# she_atmega328.net
KiCad netlist of a schematic drawn in EAGLE
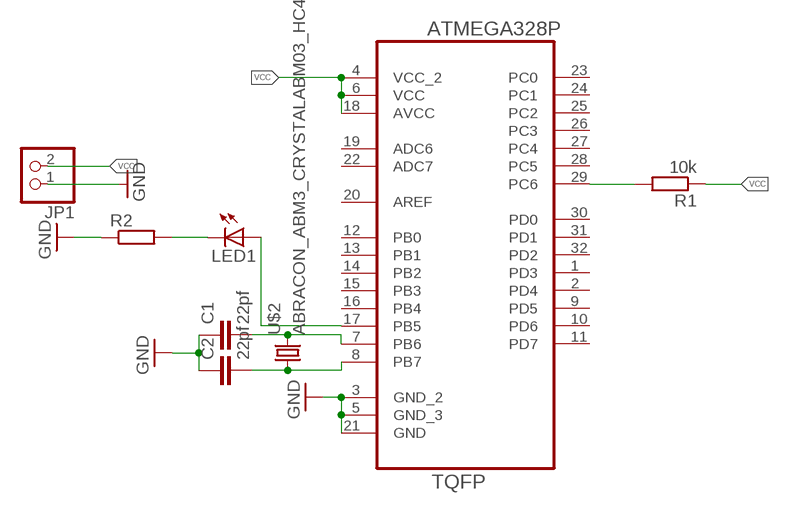
[diagram p0: schematic, sheet 1]

(export (version "E")
  (design (tool "Eeschema 10.0.6"))
  (components
    (comp (ref "C1")
      (value "22pf")
      (footprint "eagle-import:C0603")
      (libsource (lib "eagle-import") (part "C-EUC0603"))
    )
    (comp (ref "C2")
      (value "22pf")
      (footprint "eagle-import:C0603")
      (libsource (lib "eagle-import") (part "C-EUC0603"))
    )
    (comp (ref "JP1")
      (value "PINHD-1X2")
      (footprint "eagle-import:1X02")
      (libsource (lib "eagle-import") (part "PINHD-1X2"))
    )
    (comp (ref "LED1")
      (value "LEDSML0603")
      (footprint "eagle-import:SML0603")
      (libsource (lib "eagle-import") (part "LEDSML0603"))
    )
    (comp (ref "R1")
      (value "10k")
      (footprint "eagle-import:R0603")
      (libsource (lib "eagle-import") (part "R-EU_R0603"))
    )
    (comp (ref "R2")
      (value "R-EU_R0603")
      (footprint "eagle-import:R0603")
      (libsource (lib "eagle-import") (part "resistor_R-EU_R0603"))
    )
    (comp (ref "U$2")
      (value "ABRACON_ABM3_CRYSTALABM03_HC49")
      (footprint "eagle-import:ABM03_HC49")
      (libsource (lib "eagle-import") (part "ABRACON_ABM3_CRYSTALABM03_HC49"))
    )
    (comp (ref "U1")
      (value "ATMEGA328P-AU")
      (footprint "eagle-import:QFP80P900X900X120-32N")
      (libsource (lib "eagle-import") (part "ATMEGA328P-AU"))
    )
  )
  (nets
    (net (code "1") (name "GND") (class "Default")
      (node (ref "C1") (pin "1") (pinfunction "1_1") (pintype "passive"))
      (node (ref "C2") (pin "1") (pinfunction "1_1") (pintype "passive"))
      (node (ref "R2") (pin "1") (pinfunction "1_1") (pintype "passive"))
      (node (ref "U1") (pin "21") (pinfunction "GND_21") (pintype "passive"))
      (node (ref "U1") (pin "3") (pinfunction "GND_2_3") (pintype "passive"))
      (node (ref "U1") (pin "5") (pinfunction "GND_3_5") (pintype "passive"))
    )
    (net (code "2") (name "Net-(LED1-PadC)") (class "Default")
      (node (ref "LED1") (pin "C") (pinfunction "C_C") (pintype "passive"))
      (node (ref "R2") (pin "2") (pinfunction "2_2") (pintype "passive"))
    )
    (net (code "3") (name "Net-(U1-PB5)") (class "Default")
      (node (ref "LED1") (pin "A") (pinfunction "A_A") (pintype "passive"))
      (node (ref "U1") (pin "17") (pinfunction "PB5_17") (pintype "bidirectional"))
    )
    (net (code "4") (name "Net-(U1-PB6)") (class "Default")
      (node (ref "C1") (pin "2") (pinfunction "2_2") (pintype "passive"))
      (node (ref "U$2") (pin "2") (pinfunction "2_2") (pintype "passive"))
      (node (ref "U1") (pin "7") (pinfunction "PB6_7") (pintype "bidirectional"))
    )
    (net (code "5") (name "Net-(U1-PB7)") (class "Default")
      (node (ref "C2") (pin "2") (pinfunction "2_2") (pintype "passive"))
      (node (ref "U$2") (pin "1") (pinfunction "1_1") (pintype "passive"))
      (node (ref "U1") (pin "8") (pinfunction "PB7_8") (pintype "bidirectional"))
    )
    (net (code "6") (name "Net-(U1-PC6)") (class "Default")
      (node (ref "R1") (pin "2") (pinfunction "2_2") (pintype "passive"))
      (node (ref "U1") (pin "29") (pinfunction "PC6_29") (pintype "bidirectional"))
    )
    (net (code "7") (name "VCC") (class "Default")
      (node (ref "JP1") (pin "2") (pinfunction "2_2") (pintype "passive"))
      (node (ref "R1") (pin "1") (pinfunction "1_1") (pintype "passive"))
      (node (ref "U1") (pin "18") (pinfunction "AVCC_18") (pintype "power_in"))
      (node (ref "U1") (pin "4") (pinfunction "VCC_2_4") (pintype "power_in"))
      (node (ref "U1") (pin "6") (pinfunction "VCC_6") (pintype "power_in"))
    )
    (net (code "8") (name "unconnected-(JP1-Pad1)") (class "Default")
      (node (ref "JP1") (pin "1") (pinfunction "1_1") (pintype "passive"))
    )
    (net (code "9") (name "unconnected-(U1-ADC6-Pad19)") (class "Default")
      (node (ref "U1") (pin "19") (pinfunction "ADC6_19") (pintype "input"))
    )
    (net (code "10") (name "unconnected-(U1-ADC7-Pad22)") (class "Default")
      (node (ref "U1") (pin "22") (pinfunction "ADC7_22") (pintype "input"))
    )
    (net (code "11") (name "unconnected-(U1-AREF-Pad20)") (class "Default")
      (node (ref "U1") (pin "20") (pinfunction "AREF_20") (pintype "input"))
    )
    (net (code "12") (name "unconnected-(U1-PB0-Pad12)") (class "Default")
      (node (ref "U1") (pin "12") (pinfunction "PB0_12") (pintype "bidirectional"))
    )
    (net (code "13") (name "unconnected-(U1-PB1-Pad13)") (class "Default")
      (node (ref "U1") (pin "13") (pinfunction "PB1_13") (pintype "bidirectional"))
    )
    (net (code "14") (name "unconnected-(U1-PB2-Pad14)") (class "Default")
      (node (ref "U1") (pin "14") (pinfunction "PB2_14") (pintype "bidirectional"))
    )
    (net (code "15") (name "unconnected-(U1-PB3-Pad15)") (class "Default")
      (node (ref "U1") (pin "15") (pinfunction "PB3_15") (pintype "bidirectional"))
    )
    (net (code "16") (name "unconnected-(U1-PB4-Pad16)") (class "Default")
      (node (ref "U1") (pin "16") (pinfunction "PB4_16") (pintype "bidirectional"))
    )
    (net (code "17") (name "unconnected-(U1-PC0-Pad23)") (class "Default")
      (node (ref "U1") (pin "23") (pinfunction "PC0_23") (pintype "bidirectional"))
    )
    (net (code "18") (name "unconnected-(U1-PC1-Pad24)") (class "Default")
      (node (ref "U1") (pin "24") (pinfunction "PC1_24") (pintype "bidirectional"))
    )
    (net (code "19") (name "unconnected-(U1-PC2-Pad25)") (class "Default")
      (node (ref "U1") (pin "25") (pinfunction "PC2_25") (pintype "bidirectional"))
    )
    (net (code "20") (name "unconnected-(U1-PC3-Pad26)") (class "Default")
      (node (ref "U1") (pin "26") (pinfunction "PC3_26") (pintype "bidirectional"))
    )
    (net (code "21") (name "unconnected-(U1-PC4-Pad27)") (class "Default")
      (node (ref "U1") (pin "27") (pinfunction "PC4_27") (pintype "bidirectional"))
    )
    (net (code "22") (name "unconnected-(U1-PC5-Pad28)") (class "Default")
      (node (ref "U1") (pin "28") (pinfunction "PC5_28") (pintype "bidirectional"))
    )
    (net (code "23") (name "unconnected-(U1-PD0-Pad30)") (class "Default")
      (node (ref "U1") (pin "30") (pinfunction "PD0_30") (pintype "bidirectional"))
    )
    (net (code "24") (name "unconnected-(U1-PD1-Pad31)") (class "Default")
      (node (ref "U1") (pin "31") (pinfunction "PD1_31") (pintype "bidirectional"))
    )
    (net (code "25") (name "unconnected-(U1-PD2-Pad32)") (class "Default")
      (node (ref "U1") (pin "32") (pinfunction "PD2_32") (pintype "bidirectional"))
    )
    (net (code "26") (name "unconnected-(U1-PD3-Pad1)") (class "Default")
      (node (ref "U1") (pin "1") (pinfunction "PD3_1") (pintype "bidirectional"))
    )
    (net (code "27") (name "unconnected-(U1-PD4-Pad2)") (class "Default")
      (node (ref "U1") (pin "2") (pinfunction "PD4_2") (pintype "bidirectional"))
    )
    (net (code "28") (name "unconnected-(U1-PD5-Pad9)") (class "Default")
      (node (ref "U1") (pin "9") (pinfunction "PD5_9") (pintype "bidirectional"))
    )
    (net (code "29") (name "unconnected-(U1-PD6-Pad10)") (class "Default")
      (node (ref "U1") (pin "10") (pinfunction "PD6_10") (pintype "bidirectional"))
    )
    (net (code "30") (name "unconnected-(U1-PD7-Pad11)") (class "Default")
      (node (ref "U1") (pin "11") (pinfunction "PD7_11") (pintype "bidirectional"))
    )
  )
)
